# Buzzer.net
KiCad netlist of a schematic drawn in Altium Designer
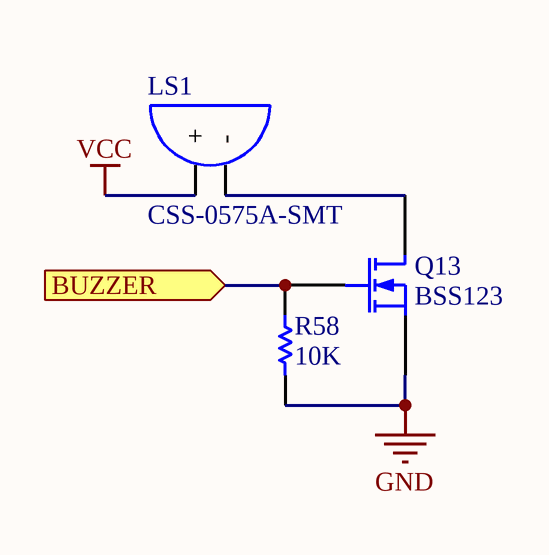
[diagram p0: Buzzer.SchDoc]

(export (version "E")
  (design (tool "Eeschema 10.0.6"))
  (components
    (comp (ref "LS1")
      (value "CSS-0575A-SMT")
      (footprint "CSS-0575A-SMT")
      (description "Magnetic Buzzer Transducer")
      (fields (field (name "MANUFACTURER") "CUI, Inc."))
      (libsource (lib "Components") (part "CSS-0575A-SMT"))
    )
    (comp (ref "Q13")
      (value "BSS123")
      (footprint "SOT323-3")
      (description "N-Channel MOSFET")
      (fields (field (name "PARTNUMBER") "BSS123WQ-7-F") (field (name "MANUFACTURER") "Diodes Incorporated"))
      (libsource (lib "MOSFETs") (part "BSS123WQ-7-F"))
    )
    (comp (ref "R58")
      (value "10K")
      (footprint "R0402[1005]")
      (description "10K 0.063W 1% 0402 (1005 Metric)")
      (fields (field (name "MANUFACTURER") "KOA Speer") (field (name "PARTNUMBER") "RK73H1ETTP1002F"))
      (libsource (lib "Resistors") (part "RES_10K_0402_1%"))
    )
  )
  (nets
    (net (code "1") (name "/BUZZER") (class "Default")
      (node (ref "Q13") (pin "1") (pinfunction "G_1") (pintype "passive"))
      (node (ref "R58") (pin "2") (pinfunction "2_2") (pintype "passive"))
    )
    (net (code "2") (name "GND") (class "Default")
      (node (ref "Q13") (pin "2") (pinfunction "S_2") (pintype "passive"))
      (node (ref "R58") (pin "1") (pinfunction "1_1") (pintype "passive"))
    )
    (net (code "3") (name "Net-(LS1--)") (class "Default")
      (node (ref "LS1") (pin "2") (pinfunction "-_2") (pintype "passive"))
      (node (ref "Q13") (pin "3") (pinfunction "D_3") (pintype "passive"))
    )
    (net (code "4") (name "VCC") (class "Default")
      (node (ref "LS1") (pin "1") (pinfunction "+_1") (pintype "passive"))
    )
  )
)
